# main.net
KiCad netlist of a schematic drawn in EAGLE
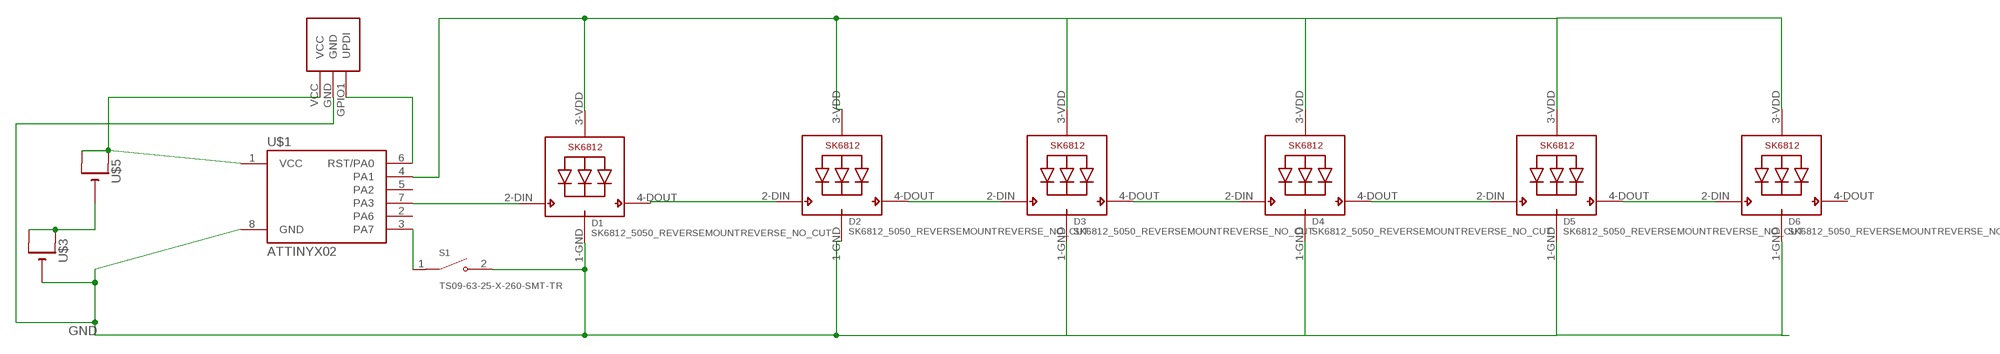
[diagram p0: schematic, sheet 1]

(export (version "E")
  (design (tool "Eeschema 10.0.6"))
  (components
    (comp (ref "D1")
      (value "SK6812_5050_REVERSEMOUNTREVERSE_NO_CUT")
      (footprint "eagle-import:SK6812_REVERSE_NO_CUT")
      (libsource (lib "eagle-import") (part "SK6812_5050_REVERSEMOUNTREVERSE_NO_CUT"))
    )
    (comp (ref "D2")
      (value "SK6812_5050_REVERSEMOUNTREVERSE_NO_CUT")
      (footprint "eagle-import:SK6812_REVERSE_NO_CUT")
      (libsource (lib "eagle-import") (part "SK6812_5050_REVERSEMOUNTREVERSE_NO_CUT"))
    )
    (comp (ref "D3")
      (value "SK6812_5050_REVERSEMOUNTREVERSE_NO_CUT")
      (footprint "eagle-import:SK6812_REVERSE_NO_CUT")
      (libsource (lib "eagle-import") (part "SK6812_5050_REVERSEMOUNTREVERSE_NO_CUT"))
    )
    (comp (ref "D4")
      (value "SK6812_5050_REVERSEMOUNTREVERSE_NO_CUT")
      (footprint "eagle-import:SK6812_REVERSE_NO_CUT")
      (libsource (lib "eagle-import") (part "SK6812_5050_REVERSEMOUNTREVERSE_NO_CUT"))
    )
    (comp (ref "D5")
      (value "SK6812_5050_REVERSEMOUNTREVERSE_NO_CUT")
      (footprint "eagle-import:SK6812_REVERSE_NO_CUT")
      (libsource (lib "eagle-import") (part "SK6812_5050_REVERSEMOUNTREVERSE_NO_CUT"))
    )
    (comp (ref "D6")
      (value "SK6812_5050_REVERSEMOUNTREVERSE_NO_CUT")
      (footprint "eagle-import:SK6812_REVERSE_NO_CUT")
      (libsource (lib "eagle-import") (part "SK6812_5050_REVERSEMOUNTREVERSE_NO_CUT"))
    )
    (comp (ref "S1")
      (value "TS09-63-25-X-260-SMT-TR")
      (footprint "eagle-import:SW_TS09-63-25-X-260-SMT-TR")
      (fields (field (name "MANUFACTURER") "CUI Devices"))
      (libsource (lib "eagle-import") (part "TS09-63-25-X-260-SMT-TR"))
    )
    (comp (ref "U$1")
      (value "ATTINYX02")
      (footprint "eagle-import:SOIC08_JEDEC_150MIL")
      (libsource (lib "eagle-import") (part "ATTINYX02"))
    )
    (comp (ref "U$2")
      (value "SAO")
      (footprint "eagle-import:SAO_SMD")
      (libsource (lib "eagle-import") (part "SAO"))
    )
    (comp (ref "U$3")
      (value "CR2032SMT")
      (footprint "eagle-import:CR2032-SMD")
      (libsource (lib "eagle-import") (part "CR2032SMT"))
    )
    (comp (ref "U$5")
      (value "CR2032SMT")
      (footprint "eagle-import:CR2032-SMD")
      (libsource (lib "eagle-import") (part "CR2032SMT"))
    )
  )
  (nets
    (net (code "1") (name "/GND") (class "Default")
      (node (ref "D1") (pin "1-GND") (pinfunction "GND_1-GND") (pintype "power_in"))
      (node (ref "D2") (pin "1-GND") (pinfunction "GND_1-GND") (pintype "power_in"))
      (node (ref "D3") (pin "1-GND") (pinfunction "GND_1-GND") (pintype "power_in"))
      (node (ref "D4") (pin "1-GND") (pinfunction "GND_1-GND") (pintype "power_in"))
      (node (ref "D5") (pin "1-GND") (pinfunction "GND_1-GND") (pintype "power_in"))
      (node (ref "D6") (pin "1-GND") (pinfunction "GND_1-GND") (pintype "power_in"))
      (node (ref "S1") (pin "2") (pinfunction "2_2") (pintype "passive"))
      (node (ref "U$1") (pin "8") (pinfunction "GND_8") (pintype "power_in"))
      (node (ref "U$2") (pin "GND") (pinfunction "GND_GND") (pintype "bidirectional"))
      (node (ref "U$3") (pin "-") (pinfunction "-_-") (pintype "passive"))
    )
    (net (code "2") (name "Net-(D1-DI)") (class "Default")
      (node (ref "D1") (pin "2-DIN") (pinfunction "DI_2-DIN") (pintype "input"))
      (node (ref "U$1") (pin "7") (pinfunction "PA3_7") (pintype "bidirectional"))
    )
    (net (code "3") (name "Net-(D1-DO)") (class "Default")
      (node (ref "D1") (pin "4-DOUT") (pinfunction "DO_4-DOUT") (pintype "output"))
      (node (ref "D2") (pin "2-DIN") (pinfunction "DI_2-DIN") (pintype "input"))
    )
    (net (code "4") (name "Net-(D1-VDD)") (class "Default")
      (node (ref "D1") (pin "3-VDD") (pinfunction "VDD_3-VDD") (pintype "power_in"))
      (node (ref "D2") (pin "3-VDD") (pinfunction "VDD_3-VDD") (pintype "power_in"))
      (node (ref "D3") (pin "3-VDD") (pinfunction "VDD_3-VDD") (pintype "power_in"))
      (node (ref "D4") (pin "3-VDD") (pinfunction "VDD_3-VDD") (pintype "power_in"))
      (node (ref "D5") (pin "3-VDD") (pinfunction "VDD_3-VDD") (pintype "power_in"))
      (node (ref "D6") (pin "3-VDD") (pinfunction "VDD_3-VDD") (pintype "power_in"))
      (node (ref "U$1") (pin "4") (pinfunction "PA1_4") (pintype "bidirectional"))
    )
    (net (code "5") (name "Net-(D2-DO)") (class "Default")
      (node (ref "D2") (pin "4-DOUT") (pinfunction "DO_4-DOUT") (pintype "output"))
      (node (ref "D3") (pin "2-DIN") (pinfunction "DI_2-DIN") (pintype "input"))
    )
    (net (code "6") (name "Net-(D3-DO)") (class "Default")
      (node (ref "D3") (pin "4-DOUT") (pinfunction "DO_4-DOUT") (pintype "output"))
      (node (ref "D4") (pin "2-DIN") (pinfunction "DI_2-DIN") (pintype "input"))
    )
    (net (code "7") (name "Net-(D4-DO)") (class "Default")
      (node (ref "D4") (pin "4-DOUT") (pinfunction "DO_4-DOUT") (pintype "output"))
      (node (ref "D5") (pin "2-DIN") (pinfunction "DI_2-DIN") (pintype "input"))
    )
    (net (code "8") (name "Net-(D5-DO)") (class "Default")
      (node (ref "D5") (pin "4-DOUT") (pinfunction "DO_4-DOUT") (pintype "output"))
      (node (ref "D6") (pin "2-DIN") (pinfunction "DI_2-DIN") (pintype "input"))
    )
    (net (code "9") (name "Net-(U$1-PA7)") (class "Default")
      (node (ref "S1") (pin "1") (pinfunction "1_1") (pintype "passive"))
      (node (ref "U$1") (pin "3") (pinfunction "PA7_3") (pintype "bidirectional"))
    )
    (net (code "10") (name "Net-(U$1-RST{slash}PA0)") (class "Default")
      (node (ref "U$1") (pin "6") (pinfunction "RST/PA0_6") (pintype "bidirectional"))
      (node (ref "U$2") (pin "GPIO1") (pinfunction "UPDI_GPIO1") (pintype "bidirectional"))
    )
    (net (code "11") (name "Net-(U$1-VCC)") (class "Default")
      (node (ref "U$1") (pin "1") (pinfunction "VCC_1") (pintype "power_in"))
      (node (ref "U$2") (pin "VCC") (pinfunction "VCC_VCC") (pintype "bidirectional"))
      (node (ref "U$5") (pin "+$1") (pinfunction "+_+$1") (pintype "passive"))
      (node (ref "U$5") (pin "+$2") (pinfunction "+1_+$2") (pintype "passive"))
    )
    (net (code "12") (name "Net-(U$3-+)") (class "Default")
      (node (ref "U$3") (pin "+$1") (pinfunction "+_+$1") (pintype "passive"))
      (node (ref "U$3") (pin "+$2") (pinfunction "+1_+$2") (pintype "passive"))
      (node (ref "U$5") (pin "-") (pinfunction "-_-") (pintype "passive"))
    )
    (net (code "13") (name "unconnected-(D6-DO-Pad4-DOUT)") (class "Default")
      (node (ref "D6") (pin "4-DOUT") (pinfunction "DO_4-DOUT") (pintype "output"))
    )
    (net (code "14") (name "unconnected-(U$1-PA2-Pad5)") (class "Default")
      (node (ref "U$1") (pin "5") (pinfunction "PA2_5") (pintype "bidirectional"))
    )
    (net (code "15") (name "unconnected-(U$1-PA6-Pad2)") (class "Default")
      (node (ref "U$1") (pin "2") (pinfunction "PA6_2") (pintype "bidirectional"))
    )
  )
)
